# host_connector.net
KiCad netlist of a schematic drawn in Altium Designer
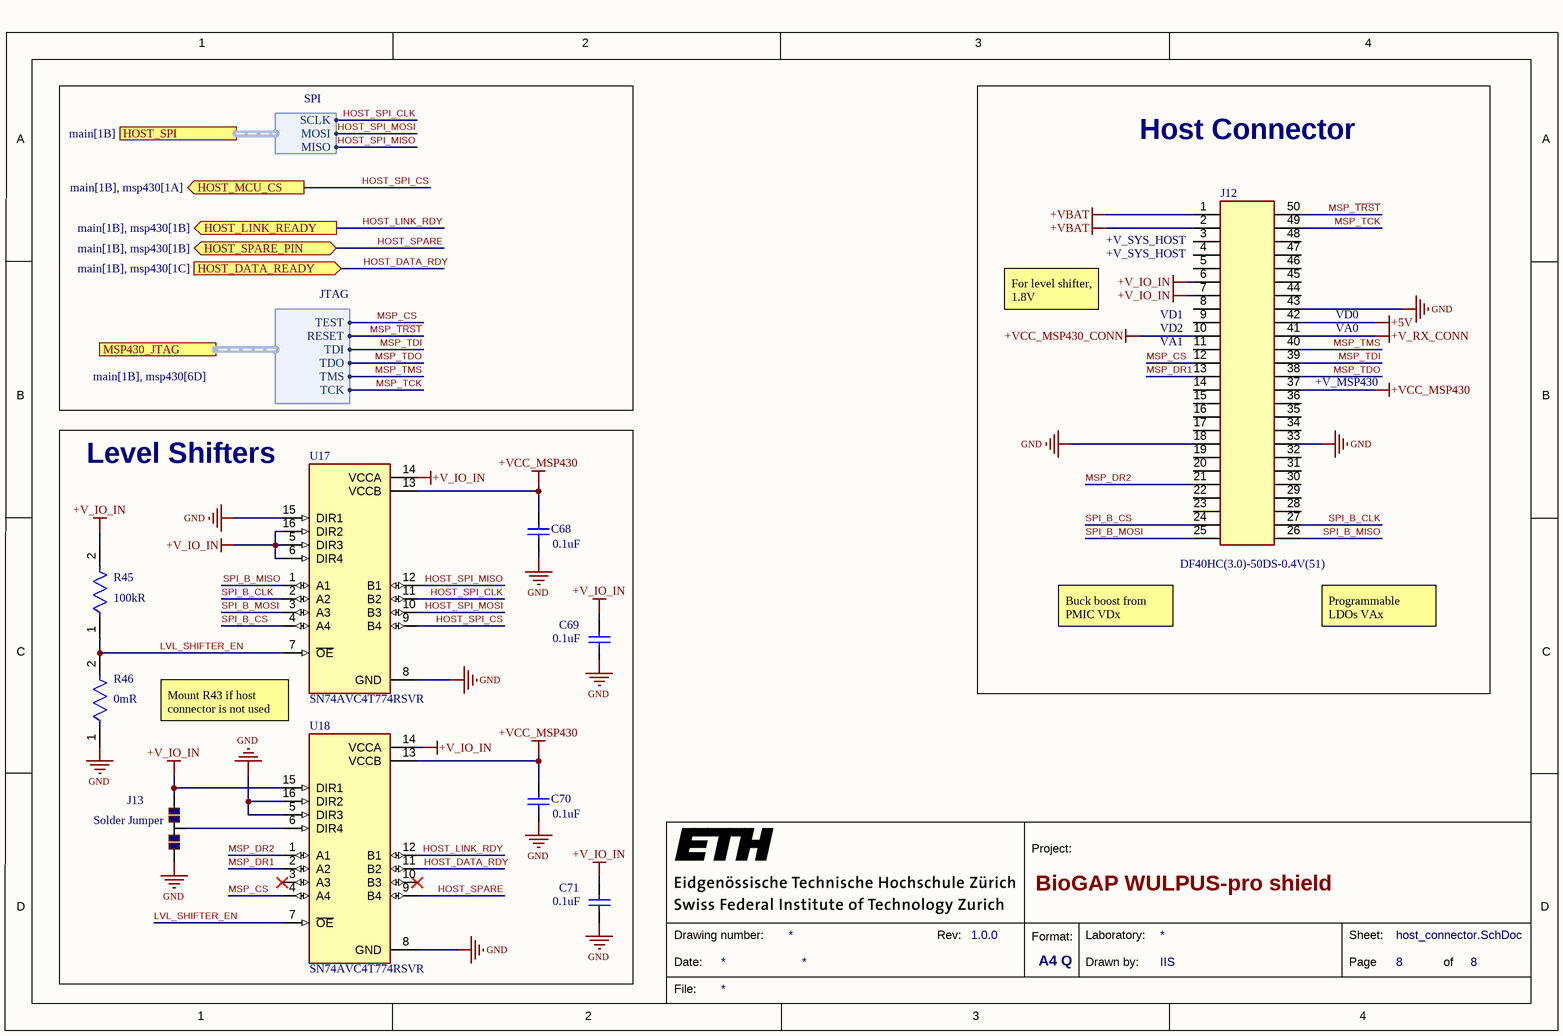
[diagram p0: host_connector.SchDoc]

(export (version "E")
  (design (tool "Eeschema 10.0.6"))
  (components
    (comp (ref "C68")
      (value "C0402C104K4RACTU")
      (footprint "CAPC1005X55X30LL05T10")
      (fields (field (name "MANUFACTURER") "Kemet") (field (name "CAPACITANCE") "0.1uF"))
      (libsource (lib "Altium Content Vault") (part "CAP"))
    )
    (comp (ref "C69")
      (value "C0402C104K4RACTU")
      (footprint "CAPC1005X55X30LL05T10")
      (fields (field (name "MANUFACTURER") "Kemet") (field (name "CAPACITANCE") "0.1uF"))
      (libsource (lib "Altium Content Vault") (part "CAP"))
    )
    (comp (ref "C70")
      (value "C0402C104K4RACTU")
      (footprint "CAPC1005X55X30LL05T10")
      (fields (field (name "MANUFACTURER") "Kemet") (field (name "CAPACITANCE") "0.1uF"))
      (libsource (lib "Altium Content Vault") (part "CAP"))
    )
    (comp (ref "C71")
      (value "C0402C104K4RACTU")
      (footprint "CAPC1005X55X30LL05T10")
      (fields (field (name "MANUFACTURER") "Kemet") (field (name "CAPACITANCE") "0.1uF"))
      (libsource (lib "Altium Content Vault") (part "CAP"))
    )
    (comp (ref "J12")
      (value "DF40HC(3.0)-50DS-0.4V(51)")
      (footprint "DF40HC3050DS04V51")
      (description "50 Position 0.4mm Pitch Dual Row Vertical Surface Mount (SMT) Pin Socket, 3.0mm Stacking Height")
      (fields (field (name "COPYRIGHT") "Copyright (C) 2023 Ultra Librarian. All rights reserved."))
      (libsource (lib "host_connectors") (part "DF40HC(3.0)-50DS-0.4V(51)"))
    )
    (comp (ref "J13")
      (value "Solder Jumper")
      (footprint "Jumper 3 pins")
      (description "Solder Jumper 3 Pads")
      (libsource (lib "ETHZ Vault") (part "Solder Jumper 3-pads"))
    )
    (comp (ref "R45")
      (value "ERJ-2RKF1003X")
      (footprint "FP-ERJ2RK-IPC_C")
      (fields (field (name "RESISTANCE") "100kR") (field (name "TOLERANCE") "1%"))
      (libsource (lib "Altium Content Vault") (part "1029c3af85768c4190bb7ad29bc67b5"))
    )
    (comp (ref "R46")
      (value "CRCW04020000Z0ED")
      (footprint "FP-CRCW0402-e3-IPC_C")
      (fields (field (name "TOLERANCE") "5%") (field (name "RESISTANCE") "0mR"))
      (libsource (lib "Altium Content Vault") (part "1029c3af85768c4190bb7ad29bc67b5"))
    )
    (comp (ref "U17")
      (value "SN74AVC4T774RSVR")
      (footprint "QFN40P260X180X55-16N")
      (description "Voltage Level Translator Bidirectional 1 Circuit 4 Channel 380Mbps 16-UQFN _2.6x1.8_")
      (fields (field (name "DIGI-KEY_PART_NUMBER") "296-24741-1-ND") (field (name "MF") "Texas Instruments"))
      (libsource (lib "SN74AVC4T774RSVR") (part "SN74AVC4T774RSVR"))
    )
    (comp (ref "U18")
      (value "SN74AVC4T774RSVR")
      (footprint "QFN40P260X180X55-16N")
      (description "Voltage Level Translator Bidirectional 1 Circuit 4 Channel 380Mbps 16-UQFN _2.6x1.8_")
      (fields (field (name "DIGI-KEY_PART_NUMBER") "296-24741-1-ND") (field (name "MF") "Texas Instruments"))
      (libsource (lib "SN74AVC4T774RSVR") (part "SN74AVC4T774RSVR"))
    )
  )
  (nets
    (net (code "3") (name "+5V") (class "Default") (node (ref "J12") (pin "42") (pintype "passive")))
    (net (code "4") (name "+VBAT") (class "Default")
      (node (ref "J12") (pin "1") (pintype "passive"))
      (node (ref "J12") (pin "2") (pintype "passive"))
    )
    (net (code "5") (name "+VCC_MSP430") (class "Default")
      (node (ref "C68") (pin "1") (pinfunction "1_1") (pintype "passive"))
      (node (ref "C70") (pin "1") (pinfunction "1_1") (pintype "passive"))
      (node (ref "J12") (pin "37") (pintype "passive"))
      (node (ref "U17") (pin "13") (pinfunction "VCCB_13") (pintype "power_in"))
      (node (ref "U18") (pin "13") (pinfunction "VCCB_13") (pintype "power_in"))
    )
    (net (code "6") (name "+VCC_MSP430_CONN") (class "Default")
      (node (ref "J12") (pin "10") (pintype "passive"))
    )
    (net (code "7") (name "+V_IO_IN") (class "Default")
      (node (ref "C69") (pin "1") (pinfunction "1_1") (pintype "passive"))
      (node (ref "C71") (pin "1") (pinfunction "1_1") (pintype "passive"))
      (node (ref "J12") (pin "6") (pintype "passive"))
      (node (ref "J12") (pin "7") (pintype "passive"))
      (node (ref "J13") (pin "3") (pinfunction "3_3") (pintype "passive"))
      (node (ref "R45") (pin "2") (pinfunction "2_2") (pintype "passive"))
      (node (ref "U17") (pin "14") (pinfunction "VCCA_14") (pintype "power_in"))
      (node (ref "U17") (pin "16") (pinfunction "DIR2_16") (pintype "input"))
      (node (ref "U17") (pin "5") (pinfunction "DIR3_5") (pintype "input"))
      (node (ref "U17") (pin "6") (pinfunction "DIR4_6") (pintype "input"))
      (node (ref "U18") (pin "14") (pinfunction "VCCA_14") (pintype "power_in"))
      (node (ref "U18") (pin "15") (pinfunction "DIR1_15") (pintype "input"))
    )
    (net (code "8") (name "+V_RX_CONN") (class "Default") (node (ref "J12") (pin "41") (pintype "passive")))
    (net (code "9") (name "/HOST_DATA_RDY") (class "Default")
      (node (ref "U18") (pin "11") (pinfunction "B2_11") (pintype "bidirectional"))
    )
    (net (code "10") (name "/HOST_LINK_RDY") (class "Default")
      (node (ref "U18") (pin "12") (pinfunction "B1_12") (pintype "bidirectional"))
    )
    (net (code "11") (name "/HOST_SPARE") (class "Default")
      (node (ref "U18") (pin "9") (pinfunction "B4_9") (pintype "bidirectional"))
    )
    (net (code "12") (name "/HOST_SPI_CLK") (class "Default")
      (node (ref "U17") (pin "11") (pinfunction "B2_11") (pintype "bidirectional"))
    )
    (net (code "13") (name "/HOST_SPI_CS") (class "Default")
      (node (ref "U17") (pin "9") (pinfunction "B4_9") (pintype "bidirectional"))
    )
    (net (code "14") (name "/HOST_SPI_MISO") (class "Default")
      (node (ref "U17") (pin "12") (pinfunction "B1_12") (pintype "bidirectional"))
    )
    (net (code "15") (name "/HOST_SPI_MOSI") (class "Default")
      (node (ref "U17") (pin "10") (pinfunction "B3_10") (pintype "bidirectional"))
    )
    (net (code "16") (name "/LVL_SHIFTER_EN") (class "Default")
      (node (ref "R45") (pin "1") (pinfunction "1_1") (pintype "passive"))
      (node (ref "R46") (pin "2") (pinfunction "2_2") (pintype "passive"))
      (node (ref "U17") (pin "7") (pinfunction "~{OE}_7") (pintype "input"))
      (node (ref "U18") (pin "7") (pinfunction "~{OE}_7") (pintype "input"))
    )
    (net (code "17") (name "/MSP_CS") (class "Default")
      (node (ref "J12") (pin "12") (pintype "passive"))
      (node (ref "U18") (pin "4") (pinfunction "A4_4") (pintype "bidirectional"))
    )
    (net (code "18") (name "/MSP_DR1") (class "Default")
      (node (ref "J12") (pin "13") (pintype "passive"))
      (node (ref "U18") (pin "2") (pinfunction "A2_2") (pintype "bidirectional"))
    )
    (net (code "19") (name "/MSP_DR2") (class "Default")
      (node (ref "J12") (pin "21") (pintype "passive"))
      (node (ref "U18") (pin "1") (pinfunction "A1_1") (pintype "bidirectional"))
    )
    (net (code "20") (name "/MSP_TCK") (class "Default") (node (ref "J12") (pin "49") (pintype "passive")))
    (net (code "21") (name "/MSP_TDI") (class "Default") (node (ref "J12") (pin "39") (pintype "passive")))
    (net (code "22") (name "/MSP_TDO") (class "Default") (node (ref "J12") (pin "38") (pintype "passive")))
    (net (code "23") (name "/MSP_TMS") (class "Default") (node (ref "J12") (pin "40") (pintype "passive")))
    (net (code "24") (name "/MSP_~{TRST}") (class "Default")
      (node (ref "J12") (pin "50") (pintype "passive"))
    )
    (net (code "25") (name "/SPI_B_CLK") (class "Default")
      (node (ref "J12") (pin "27") (pintype "passive"))
      (node (ref "U17") (pin "2") (pinfunction "A2_2") (pintype "bidirectional"))
    )
    (net (code "26") (name "/SPI_B_CS") (class "Default")
      (node (ref "J12") (pin "24") (pintype "passive"))
      (node (ref "U17") (pin "4") (pinfunction "A4_4") (pintype "bidirectional"))
    )
    (net (code "27") (name "/SPI_B_MISO") (class "Default")
      (node (ref "J12") (pin "26") (pintype "passive"))
      (node (ref "U17") (pin "1") (pinfunction "A1_1") (pintype "bidirectional"))
    )
    (net (code "28") (name "/SPI_B_MOSI") (class "Default")
      (node (ref "J12") (pin "25") (pintype "passive"))
      (node (ref "U17") (pin "3") (pinfunction "A3_3") (pintype "bidirectional"))
    )
    (net (code "31") (name "GND") (class "Default")
      (node (ref "C68") (pin "2") (pinfunction "2_2") (pintype "passive"))
      (node (ref "C69") (pin "2") (pinfunction "2_2") (pintype "passive"))
      (node (ref "C70") (pin "2") (pinfunction "2_2") (pintype "passive"))
      (node (ref "C71") (pin "2") (pinfunction "2_2") (pintype "passive"))
      (node (ref "J12") (pin "18") (pintype "passive"))
      (node (ref "J12") (pin "33") (pintype "passive"))
      (node (ref "J12") (pin "43") (pintype "passive"))
      (node (ref "J13") (pin "1") (pinfunction "1_1") (pintype "passive"))
      (node (ref "R46") (pin "1") (pinfunction "1_1") (pintype "passive"))
      (node (ref "U17") (pin "15") (pinfunction "DIR1_15") (pintype "input"))
      (node (ref "U17") (pin "8") (pinfunction "GND_8") (pintype "power_in"))
      (node (ref "U18") (pin "16") (pinfunction "DIR2_16") (pintype "input"))
      (node (ref "U18") (pin "5") (pinfunction "DIR3_5") (pintype "input"))
      (node (ref "U18") (pin "8") (pinfunction "GND_8") (pintype "power_in"))
    )
    (net (code "32") (name "Net-(U18-DIR4)") (class "Default")
      (node (ref "J13") (pin "2") (pinfunction "2_2") (pintype "passive"))
      (node (ref "U18") (pin "6") (pinfunction "DIR4_6") (pintype "input"))
    )
    (net (code "33") (name "unconnected-(J12-Pad3)") (class "Default")
      (node (ref "J12") (pin "3") (pintype "passive"))
    )
    (net (code "34") (name "unconnected-(J12-Pad4)") (class "Default")
      (node (ref "J12") (pin "4") (pintype "passive"))
    )
    (net (code "35") (name "unconnected-(J12-Pad5)") (class "Default")
      (node (ref "J12") (pin "5") (pintype "passive"))
    )
    (net (code "36") (name "unconnected-(J12-Pad8)") (class "Default")
      (node (ref "J12") (pin "8") (pintype "passive"))
    )
    (net (code "37") (name "unconnected-(J12-Pad9)") (class "Default")
      (node (ref "J12") (pin "9") (pintype "passive"))
    )
    (net (code "38") (name "unconnected-(J12-Pad11)") (class "Default")
      (node (ref "J12") (pin "11") (pintype "passive"))
    )
    (net (code "39") (name "unconnected-(J12-Pad14)") (class "Default")
      (node (ref "J12") (pin "14") (pintype "passive"))
    )
    (net (code "40") (name "unconnected-(J12-Pad15)") (class "Default")
      (node (ref "J12") (pin "15") (pintype "passive"))
    )
    (net (code "41") (name "unconnected-(J12-Pad16)") (class "Default")
      (node (ref "J12") (pin "16") (pintype "passive"))
    )
    (net (code "42") (name "unconnected-(J12-Pad17)") (class "Default")
      (node (ref "J12") (pin "17") (pintype "passive"))
    )
    (net (code "43") (name "unconnected-(J12-Pad19)") (class "Default")
      (node (ref "J12") (pin "19") (pintype "passive"))
    )
    (net (code "44") (name "unconnected-(J12-Pad20)") (class "Default")
      (node (ref "J12") (pin "20") (pintype "passive"))
    )
    (net (code "45") (name "unconnected-(J12-Pad22)") (class "Default")
      (node (ref "J12") (pin "22") (pintype "passive"))
    )
    (net (code "46") (name "unconnected-(J12-Pad23)") (class "Default")
      (node (ref "J12") (pin "23") (pintype "passive"))
    )
    (net (code "47") (name "unconnected-(J12-Pad28)") (class "Default")
      (node (ref "J12") (pin "28") (pintype "passive"))
    )
    (net (code "48") (name "unconnected-(J12-Pad29)") (class "Default")
      (node (ref "J12") (pin "29") (pintype "passive"))
    )
    (net (code "49") (name "unconnected-(J12-Pad30)") (class "Default")
      (node (ref "J12") (pin "30") (pintype "passive"))
    )
    (net (code "50") (name "unconnected-(J12-Pad31)") (class "Default")
      (node (ref "J12") (pin "31") (pintype "passive"))
    )
    (net (code "51") (name "unconnected-(J12-Pad32)") (class "Default")
      (node (ref "J12") (pin "32") (pintype "passive"))
    )
    (net (code "52") (name "unconnected-(J12-Pad34)") (class "Default")
      (node (ref "J12") (pin "34") (pintype "passive"))
    )
    (net (code "53") (name "unconnected-(J12-Pad35)") (class "Default")
      (node (ref "J12") (pin "35") (pintype "passive"))
    )
    (net (code "54") (name "unconnected-(J12-Pad36)") (class "Default")
      (node (ref "J12") (pin "36") (pintype "passive"))
    )
    (net (code "55") (name "unconnected-(J12-Pad44)") (class "Default")
      (node (ref "J12") (pin "44") (pintype "passive"))
    )
    (net (code "56") (name "unconnected-(J12-Pad45)") (class "Default")
      (node (ref "J12") (pin "45") (pintype "passive"))
    )
    (net (code "57") (name "unconnected-(J12-Pad46)") (class "Default")
      (node (ref "J12") (pin "46") (pintype "passive"))
    )
    (net (code "58") (name "unconnected-(J12-Pad47)") (class "Default")
      (node (ref "J12") (pin "47") (pintype "passive"))
    )
    (net (code "59") (name "unconnected-(J12-Pad48)") (class "Default")
      (node (ref "J12") (pin "48") (pintype "passive"))
    )
    (net (code "60") (name "unconnected-(U18-A3-Pad3)") (class "Default")
      (node (ref "U18") (pin "3") (pinfunction "A3_3") (pintype "bidirectional+no_connect"))
    )
    (net (code "61") (name "unconnected-(U18-B3-Pad10)") (class "Default")
      (node (ref "U18") (pin "10") (pinfunction "B3_10") (pintype "bidirectional+no_connect"))
    )
  )
)
